# V2_SENSOR.net
KiCad netlist of a schematic drawn in EAGLE
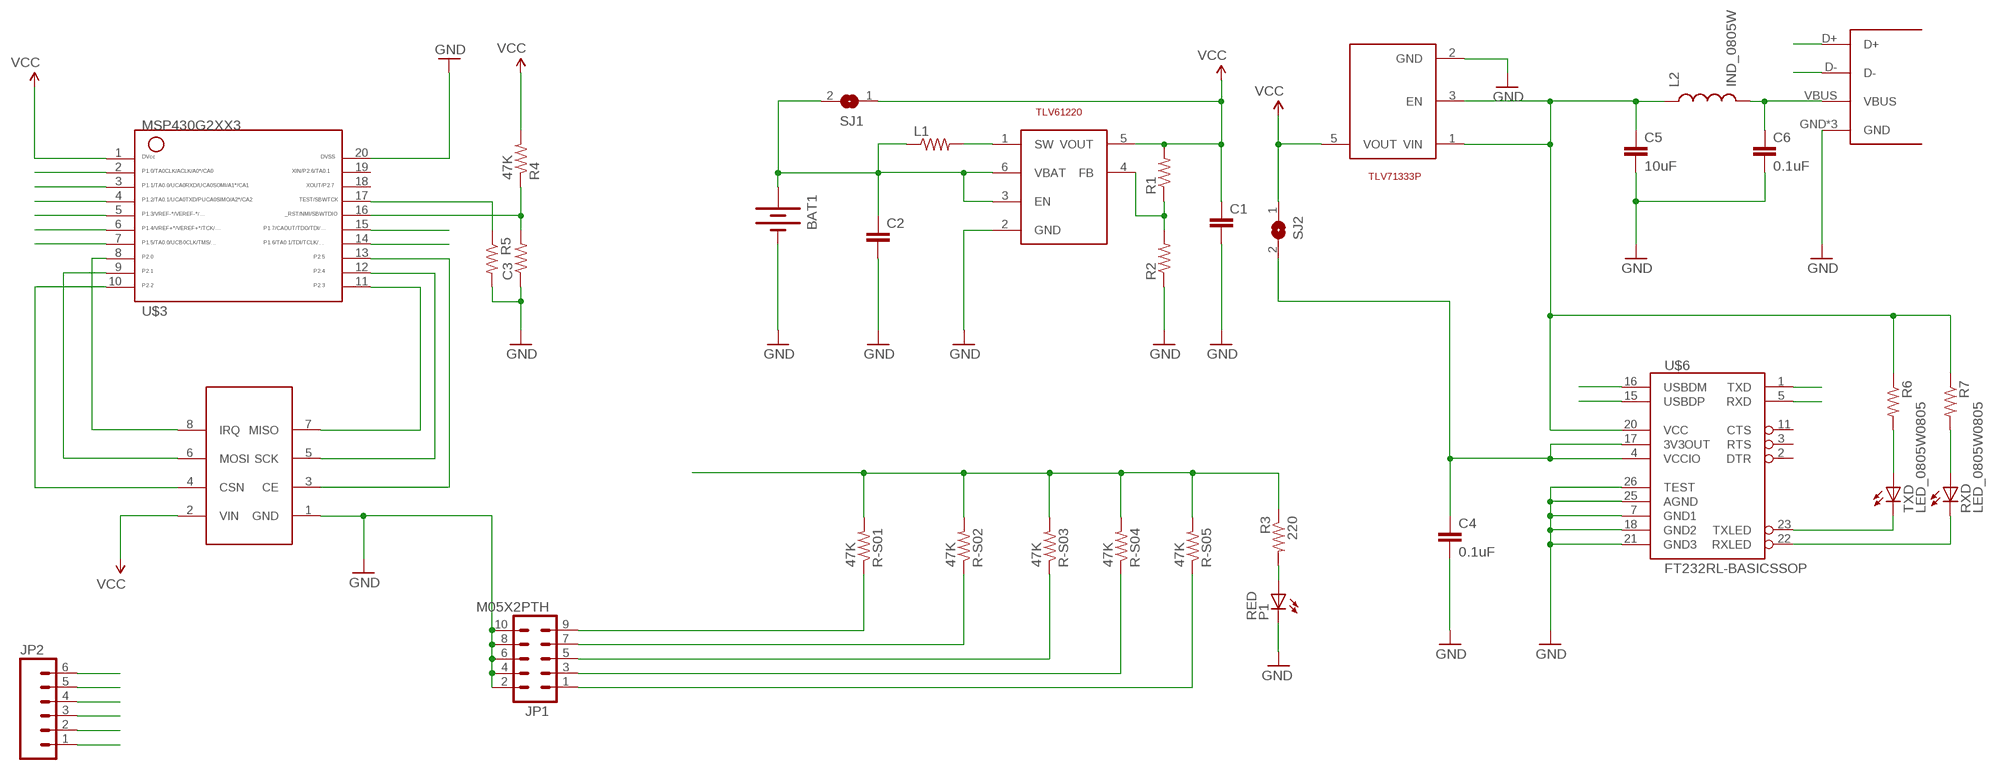
[diagram p0: schematic, sheet 1]

(export (version "E")
  (design (tool "Eeschema 10.0.6"))
  (components
    (comp (ref "BAT1")
      (value "BATTERY20PTH")
      (footprint "eagle-import:BATTCOM_20MM_PTH")
      (libsource (lib "eagle-import") (part "BATTERY20PTH"))
    )
    (comp (ref "C1")
      (value "CAP_0805W")
      (footprint "eagle-import:0805W")
      (libsource (lib "eagle-import") (part "CAP_0805W"))
    )
    (comp (ref "C2")
      (value "CAP_0805W")
      (footprint "eagle-import:0805W")
      (libsource (lib "eagle-import") (part "CAP_0805W"))
    )
    (comp (ref "C3")
      (value "RES_0805W")
      (footprint "eagle-import:0805W")
      (libsource (lib "eagle-import") (part "RES_0805W"))
    )
    (comp (ref "C4")
      (value "0.1uF")
      (footprint "eagle-import:0805W")
      (libsource (lib "eagle-import") (part "CAP_0805W"))
    )
    (comp (ref "C5")
      (value "10uF")
      (footprint "eagle-import:0805W")
      (libsource (lib "eagle-import") (part "CAP_0805W"))
    )
    (comp (ref "C6")
      (value "0.1uF")
      (footprint "eagle-import:0805W")
      (libsource (lib "eagle-import") (part "CAP_0805W"))
    )
    (comp (ref "JP1")
      (value "M05X2PTH")
      (footprint "eagle-import:AVR_ICSP")
      (libsource (lib "eagle-import") (part "M05X2PTH"))
    )
    (comp (ref "JP2")
      (value "M06SIP")
      (footprint "eagle-import:1X06")
      (libsource (lib "eagle-import") (part "M06SIP"))
    )
    (comp (ref "JP4")
      (value "USB-A-H")
      (footprint "eagle-import:USB-A-H")
      (libsource (lib "eagle-import") (part "USB-A-H"))
    )
    (comp (ref "L1")
      (value "RES_0805W")
      (footprint "eagle-import:0805W")
      (libsource (lib "eagle-import") (part "RES_0805W"))
    )
    (comp (ref "L2")
      (value "IND_0805W")
      (footprint "eagle-import:0805W")
      (libsource (lib "eagle-import") (part "IND_0805W"))
    )
    (comp (ref "P1")
      (value "RED")
      (footprint "eagle-import:0805W_LED")
      (libsource (lib "eagle-import") (part "LED_0805W0805"))
    )
    (comp (ref "R-S01")
      (value "47K")
      (footprint "eagle-import:0805W")
      (libsource (lib "eagle-import") (part "RES_0805W"))
    )
    (comp (ref "R-S02")
      (value "47K")
      (footprint "eagle-import:0805W")
      (libsource (lib "eagle-import") (part "RES_0805W"))
    )
    (comp (ref "R-S03")
      (value "47K")
      (footprint "eagle-import:0805W")
      (libsource (lib "eagle-import") (part "RES_0805W"))
    )
    (comp (ref "R-S04")
      (value "47K")
      (footprint "eagle-import:0805W")
      (libsource (lib "eagle-import") (part "RES_0805W"))
    )
    (comp (ref "R-S05")
      (value "47K")
      (footprint "eagle-import:0805W")
      (libsource (lib "eagle-import") (part "RES_0805W"))
    )
    (comp (ref "R1")
      (value "RES_0805W")
      (footprint "eagle-import:0805W")
      (libsource (lib "eagle-import") (part "RES_0805W"))
    )
    (comp (ref "R2")
      (value "RES_0805W")
      (footprint "eagle-import:0805W")
      (libsource (lib "eagle-import") (part "RES_0805W"))
    )
    (comp (ref "R3")
      (value "220")
      (footprint "eagle-import:0805W")
      (libsource (lib "eagle-import") (part "RES_0805W"))
    )
    (comp (ref "R4")
      (value "47K")
      (footprint "eagle-import:0805W")
      (libsource (lib "eagle-import") (part "RES_0805W"))
    )
    (comp (ref "R5")
      (value "RES_0805W")
      (footprint "eagle-import:0805W")
      (libsource (lib "eagle-import") (part "RES_0805W"))
    )
    (comp (ref "R6")
      (value "RES_0805W")
      (footprint "eagle-import:0805W")
      (libsource (lib "eagle-import") (part "RES_0805W"))
    )
    (comp (ref "R7")
      (value "RES_0805W")
      (footprint "eagle-import:0805W")
      (libsource (lib "eagle-import") (part "RES_0805W"))
    )
    (comp (ref "RXD")
      (value "LED_0805W0805")
      (footprint "eagle-import:0805W_LED")
      (libsource (lib "eagle-import") (part "LED_0805W0805"))
    )
    (comp (ref "SJ1") (value "SJ") (footprint "eagle-import:SJ") (libsource (lib "eagle-import") (part "SJ")))
    (comp (ref "SJ2") (value "SJ") (footprint "eagle-import:SJ") (libsource (lib "eagle-import") (part "SJ")))
    (comp (ref "TXD")
      (value "LED_0805W0805")
      (footprint "eagle-import:0805W_LED")
      (libsource (lib "eagle-import") (part "LED_0805W0805"))
    )
    (comp (ref "U$2")
      (value "TLV61220")
      (footprint "eagle-import:SOT23-6L")
      (libsource (lib "eagle-import") (part "TI-TLV61220"))
    )
    (comp (ref "U$3")
      (value "G2XX3---N20")
      (footprint "eagle-import:N20")
      (libsource (lib "eagle-import") (part "G2XX3---N20"))
    )
    (comp (ref "U$5")
      (value "TI-TLV71333P")
      (footprint "eagle-import:SOT23-5")
      (libsource (lib "eagle-import") (part "TI-TLV71333P"))
    )
    (comp (ref "U$6")
      (value "FT232RL-BASICSSOP")
      (footprint "eagle-import:SSOP28DB")
      (libsource (lib "eagle-import") (part "FT232RL-BASICSSOP"))
    )
    (comp (ref "U1")
      (value "NRF24L01-4X2")
      (footprint "eagle-import:NRF24L01-4X2")
      (libsource (lib "eagle-import") (part "NRF24L01-4X2"))
    )
  )
  (nets
    (net (code "1") (name "/RESET") (class "Default")
      (node (ref "C3") (pin "2") (pinfunction "2_2") (pintype "passive"))
      (node (ref "JP2") (pin "3") (pinfunction "3_3") (pintype "passive"))
      (node (ref "R4") (pin "1") (pinfunction "1_1") (pintype "passive"))
      (node (ref "U$3") (pin "16") (pinfunction "16_16") (pintype "bidirectional"))
    )
    (net (code "2") (name "/RXD") (class "Default")
      (node (ref "JP2") (pin "5") (pinfunction "5_5") (pintype "passive"))
      (node (ref "U$3") (pin "3") (pinfunction "3_3") (pintype "bidirectional"))
      (node (ref "U$6") (pin "1") (pinfunction "TXD_1") (pintype "output"))
    )
    (net (code "3") (name "/S1") (class "Default")
      (node (ref "JP1") (pin "9") (pinfunction "9_9") (pintype "passive"))
      (node (ref "R-S01") (pin "1") (pinfunction "1_1") (pintype "passive"))
      (node (ref "U$3") (pin "5") (pinfunction "5_5") (pintype "bidirectional"))
    )
    (net (code "4") (name "/S2") (class "Default")
      (node (ref "JP1") (pin "7") (pinfunction "7_7") (pintype "passive"))
      (node (ref "R-S02") (pin "1") (pinfunction "1_1") (pintype "passive"))
      (node (ref "U$3") (pin "6") (pinfunction "6_6") (pintype "bidirectional"))
    )
    (net (code "5") (name "/S3") (class "Default")
      (node (ref "JP1") (pin "5") (pinfunction "5_5") (pintype "passive"))
      (node (ref "R-S03") (pin "1") (pinfunction "1_1") (pintype "passive"))
      (node (ref "U$3") (pin "7") (pinfunction "7_7") (pintype "bidirectional"))
    )
    (net (code "6") (name "/S4") (class "Default")
      (node (ref "JP1") (pin "3") (pinfunction "3_3") (pintype "passive"))
      (node (ref "R-S04") (pin "1") (pinfunction "1_1") (pintype "passive"))
      (node (ref "U$3") (pin "14") (pinfunction "14_14") (pintype "bidirectional"))
    )
    (net (code "7") (name "/S5") (class "Default")
      (node (ref "JP1") (pin "1") (pinfunction "1_1") (pintype "passive"))
      (node (ref "R-S05") (pin "1") (pinfunction "1_1") (pintype "passive"))
      (node (ref "U$3") (pin "15") (pinfunction "15_15") (pintype "bidirectional"))
    )
    (net (code "8") (name "/SV") (class "Default")
      (node (ref "R-S01") (pin "2") (pinfunction "2_2") (pintype "passive"))
      (node (ref "R-S02") (pin "2") (pinfunction "2_2") (pintype "passive"))
      (node (ref "R-S03") (pin "2") (pinfunction "2_2") (pintype "passive"))
      (node (ref "R-S04") (pin "2") (pinfunction "2_2") (pintype "passive"))
      (node (ref "R-S05") (pin "2") (pinfunction "2_2") (pintype "passive"))
      (node (ref "R3") (pin "1") (pinfunction "1_1") (pintype "passive"))
      (node (ref "U$3") (pin "2") (pinfunction "2_2") (pintype "bidirectional"))
    )
    (net (code "9") (name "/TEST") (class "Default")
      (node (ref "JP2") (pin "2") (pinfunction "2_2") (pintype "passive"))
      (node (ref "R5") (pin "1") (pinfunction "1_1") (pintype "passive"))
      (node (ref "U$3") (pin "17") (pinfunction "17_17") (pintype "bidirectional"))
    )
    (net (code "10") (name "/TXD") (class "Default")
      (node (ref "JP2") (pin "4") (pinfunction "4_4") (pintype "passive"))
      (node (ref "U$3") (pin "4") (pinfunction "4_4") (pintype "bidirectional"))
      (node (ref "U$6") (pin "5") (pinfunction "RXD_5") (pintype "input"))
    )
    (net (code "11") (name "/USBDM") (class "Default")
      (node (ref "JP4") (pin "D-") (pinfunction "D-_D-") (pintype "bidirectional"))
      (node (ref "U$6") (pin "16") (pinfunction "USBDM_16") (pintype "bidirectional"))
    )
    (net (code "12") (name "/USBDP") (class "Default")
      (node (ref "JP4") (pin "D+") (pinfunction "D+_D+") (pintype "bidirectional"))
      (node (ref "U$6") (pin "15") (pinfunction "USBDP_15") (pintype "bidirectional"))
    )
    (net (code "13") (name "GND") (class "Default")
      (node (ref "BAT1") (pin "2") (pinfunction "-_2") (pintype "power_in"))
      (node (ref "C1") (pin "2") (pinfunction "2_2") (pintype "passive"))
      (node (ref "C2") (pin "2") (pinfunction "2_2") (pintype "passive"))
      (node (ref "C3") (pin "1") (pinfunction "1_1") (pintype "passive"))
      (node (ref "C4") (pin "2") (pinfunction "2_2") (pintype "passive"))
      (node (ref "C5") (pin "2") (pinfunction "2_2") (pintype "passive"))
      (node (ref "C6") (pin "2") (pinfunction "2_2") (pintype "passive"))
      (node (ref "JP1") (pin "10") (pinfunction "10_10") (pintype "passive"))
      (node (ref "JP1") (pin "2") (pinfunction "2_2") (pintype "passive"))
      (node (ref "JP1") (pin "4") (pinfunction "4_4") (pintype "passive"))
      (node (ref "JP1") (pin "6") (pinfunction "6_6") (pintype "passive"))
      (node (ref "JP1") (pin "8") (pinfunction "8_8") (pintype "passive"))
      (node (ref "JP2") (pin "6") (pinfunction "6_6") (pintype "passive"))
      (node (ref "JP4") (pin "GND") (pinfunction "GND_GND") (pintype "bidirectional"))
      (node (ref "JP4") (pin "GND2") (pinfunction "GND_GND2") (pintype "bidirectional"))
      (node (ref "JP4") (pin "GND3") (pinfunction "GND_GND3") (pintype "bidirectional"))
      (node (ref "P1") (pin "C") (pinfunction "C_C") (pintype "passive"))
      (node (ref "R2") (pin "1") (pinfunction "1_1") (pintype "passive"))
      (node (ref "R5") (pin "2") (pinfunction "2_2") (pintype "passive"))
      (node (ref "U$2") (pin "2") (pinfunction "GND_2") (pintype "power_in"))
      (node (ref "U$3") (pin "20") (pinfunction "20_20") (pintype "bidirectional"))
      (node (ref "U$5") (pin "2") (pinfunction "GND_2") (pintype "power_in"))
      (node (ref "U$6") (pin "18") (pinfunction "GND2_18") (pintype "power_in"))
      (node (ref "U$6") (pin "21") (pinfunction "GND3_21") (pintype "power_in"))
      (node (ref "U$6") (pin "25") (pinfunction "AGND_25") (pintype "power_in"))
      (node (ref "U$6") (pin "26") (pinfunction "TEST_26") (pintype "input"))
      (node (ref "U$6") (pin "7") (pinfunction "GND1_7") (pintype "power_in"))
      (node (ref "U1") (pin "1") (pinfunction "GND_1") (pintype "power_in"))
    )
    (net (code "14") (name "Net-(BAT1-+)") (class "Default")
      (node (ref "BAT1") (pin "1") (pinfunction "+_1") (pintype "power_in"))
      (node (ref "C2") (pin "1") (pinfunction "1_1") (pintype "passive"))
      (node (ref "L1") (pin "1") (pinfunction "1_1") (pintype "passive"))
      (node (ref "SJ1") (pin "2") (pinfunction "2_2") (pintype "passive"))
      (node (ref "U$2") (pin "3") (pinfunction "EN_3") (pintype "input"))
      (node (ref "U$2") (pin "6") (pinfunction "VBAT_6") (pintype "power_in"))
    )
    (net (code "15") (name "Net-(C6-Pad1)") (class "Default")
      (node (ref "C6") (pin "1") (pinfunction "1_1") (pintype "passive"))
      (node (ref "JP4") (pin "VBUS") (pinfunction "VBUS_VBUS") (pintype "bidirectional"))
      (node (ref "L2") (pin "2") (pinfunction "2_2") (pintype "passive"))
    )
    (net (code "16") (name "Net-(P1-PadA)") (class "Default")
      (node (ref "P1") (pin "A") (pinfunction "A_A") (pintype "passive"))
      (node (ref "R3") (pin "2") (pinfunction "2_2") (pintype "passive"))
    )
    (net (code "17") (name "Net-(R6-Pad2)") (class "Default")
      (node (ref "R6") (pin "2") (pinfunction "2_2") (pintype "passive"))
      (node (ref "TXD") (pin "A") (pinfunction "A_A") (pintype "passive"))
    )
    (net (code "18") (name "Net-(R7-Pad2)") (class "Default")
      (node (ref "R7") (pin "2") (pinfunction "2_2") (pintype "passive"))
      (node (ref "RXD") (pin "A") (pinfunction "A_A") (pintype "passive"))
    )
    (net (code "19") (name "Net-(U$2-FB)") (class "Default")
      (node (ref "R1") (pin "1") (pinfunction "1_1") (pintype "passive"))
      (node (ref "R2") (pin "2") (pinfunction "2_2") (pintype "passive"))
      (node (ref "U$2") (pin "4") (pinfunction "FB_4") (pintype "input"))
    )
    (net (code "20") (name "Net-(U$2-SW)") (class "Default")
      (node (ref "L1") (pin "2") (pinfunction "2_2") (pintype "passive"))
      (node (ref "U$2") (pin "1") (pinfunction "SW_1") (pintype "power_in"))
    )
    (net (code "21") (name "Net-(U$5-EN)") (class "Default")
      (node (ref "C5") (pin "1") (pinfunction "1_1") (pintype "passive"))
      (node (ref "L2") (pin "1") (pinfunction "1_1") (pintype "passive"))
      (node (ref "R6") (pin "1") (pinfunction "1_1") (pintype "passive"))
      (node (ref "R7") (pin "1") (pinfunction "1_1") (pintype "passive"))
      (node (ref "U$5") (pin "1") (pinfunction "VIN_1") (pintype "power_in"))
      (node (ref "U$5") (pin "3") (pinfunction "EN_3") (pintype "input"))
      (node (ref "U$6") (pin "20") (pinfunction "VCC_20") (pintype "power_in"))
    )
    (net (code "22") (name "Net-(U$6-3V3OUT)") (class "Default")
      (node (ref "C4") (pin "1") (pinfunction "1_1") (pintype "passive"))
      (node (ref "SJ2") (pin "2") (pinfunction "2_2") (pintype "passive"))
      (node (ref "U$6") (pin "17") (pinfunction "3V3OUT_17") (pintype "output"))
      (node (ref "U$6") (pin "4") (pinfunction "VCCIO_4") (pintype "power_in"))
    )
    (net (code "23") (name "Net-(U$6-RXLED)") (class "Default")
      (node (ref "RXD") (pin "C") (pinfunction "C_C") (pintype "passive"))
      (node (ref "U$6") (pin "22") (pinfunction "RXLED_22") (pintype "bidirectional"))
    )
    (net (code "24") (name "Net-(U$6-TXLED)") (class "Default")
      (node (ref "TXD") (pin "C") (pinfunction "C_C") (pintype "passive"))
      (node (ref "U$6") (pin "23") (pinfunction "TXLED_23") (pintype "bidirectional"))
    )
    (net (code "25") (name "Net-(U1-CE)") (class "Default")
      (node (ref "U$3") (pin "13") (pinfunction "13_13") (pintype "bidirectional"))
      (node (ref "U1") (pin "3") (pinfunction "CE_3") (pintype "input"))
    )
    (net (code "26") (name "Net-(U1-CSN)") (class "Default")
      (node (ref "U$3") (pin "10") (pinfunction "10_10") (pintype "bidirectional"))
      (node (ref "U1") (pin "4") (pinfunction "CSN_4") (pintype "input"))
    )
    (net (code "27") (name "Net-(U1-IRQ)") (class "Default")
      (node (ref "U$3") (pin "8") (pinfunction "8_8") (pintype "bidirectional"))
      (node (ref "U1") (pin "8") (pinfunction "IRQ_8") (pintype "output"))
    )
    (net (code "28") (name "Net-(U1-MISO)") (class "Default")
      (node (ref "U$3") (pin "11") (pinfunction "11_11") (pintype "bidirectional"))
      (node (ref "U1") (pin "7") (pinfunction "MISO_7") (pintype "output"))
    )
    (net (code "29") (name "Net-(U1-MOSI)") (class "Default")
      (node (ref "U$3") (pin "9") (pinfunction "9_9") (pintype "bidirectional"))
      (node (ref "U1") (pin "6") (pinfunction "MOSI_6") (pintype "input"))
    )
    (net (code "30") (name "Net-(U1-SCK)") (class "Default")
      (node (ref "U$3") (pin "12") (pinfunction "12_12") (pintype "bidirectional"))
      (node (ref "U1") (pin "5") (pinfunction "SCK_5") (pintype "input"))
    )
    (net (code "31") (name "VCC") (class "Default")
      (node (ref "C1") (pin "1") (pinfunction "1_1") (pintype "passive"))
      (node (ref "JP2") (pin "1") (pinfunction "1_1") (pintype "passive"))
      (node (ref "R1") (pin "2") (pinfunction "2_2") (pintype "passive"))
      (node (ref "R4") (pin "2") (pinfunction "2_2") (pintype "passive"))
      (node (ref "SJ1") (pin "1") (pinfunction "1_1") (pintype "passive"))
      (node (ref "SJ2") (pin "1") (pinfunction "1_1") (pintype "passive"))
      (node (ref "U$2") (pin "5") (pinfunction "VOUT_5") (pintype "power_in"))
      (node (ref "U$3") (pin "1") (pinfunction "1_1") (pintype "bidirectional"))
      (node (ref "U$5") (pin "5") (pinfunction "VOUT_5") (pintype "power_in"))
      (node (ref "U1") (pin "2") (pinfunction "VIN_2") (pintype "power_in"))
    )
    (net (code "32") (name "unconnected-(U$3-Pad18)") (class "Default")
      (node (ref "U$3") (pin "18") (pinfunction "18_18") (pintype "bidirectional"))
    )
    (net (code "33") (name "unconnected-(U$3-Pad19)") (class "Default")
      (node (ref "U$3") (pin "19") (pinfunction "19_19") (pintype "bidirectional"))
    )
    (net (code "34") (name "unconnected-(U$6-CTS-Pad11)") (class "Default")
      (node (ref "U$6") (pin "11") (pinfunction "CTS_11") (pintype "bidirectional"))
    )
    (net (code "35") (name "unconnected-(U$6-DTR-Pad2)") (class "Default")
      (node (ref "U$6") (pin "2") (pinfunction "DTR_2") (pintype "bidirectional"))
    )
    (net (code "36") (name "unconnected-(U$6-RTS-Pad3)") (class "Default")
      (node (ref "U$6") (pin "3") (pinfunction "RTS_3") (pintype "bidirectional"))
    )
  )
)
